# STM32F103C8T6.net
KiCad netlist of a schematic drawn in Altium Designer
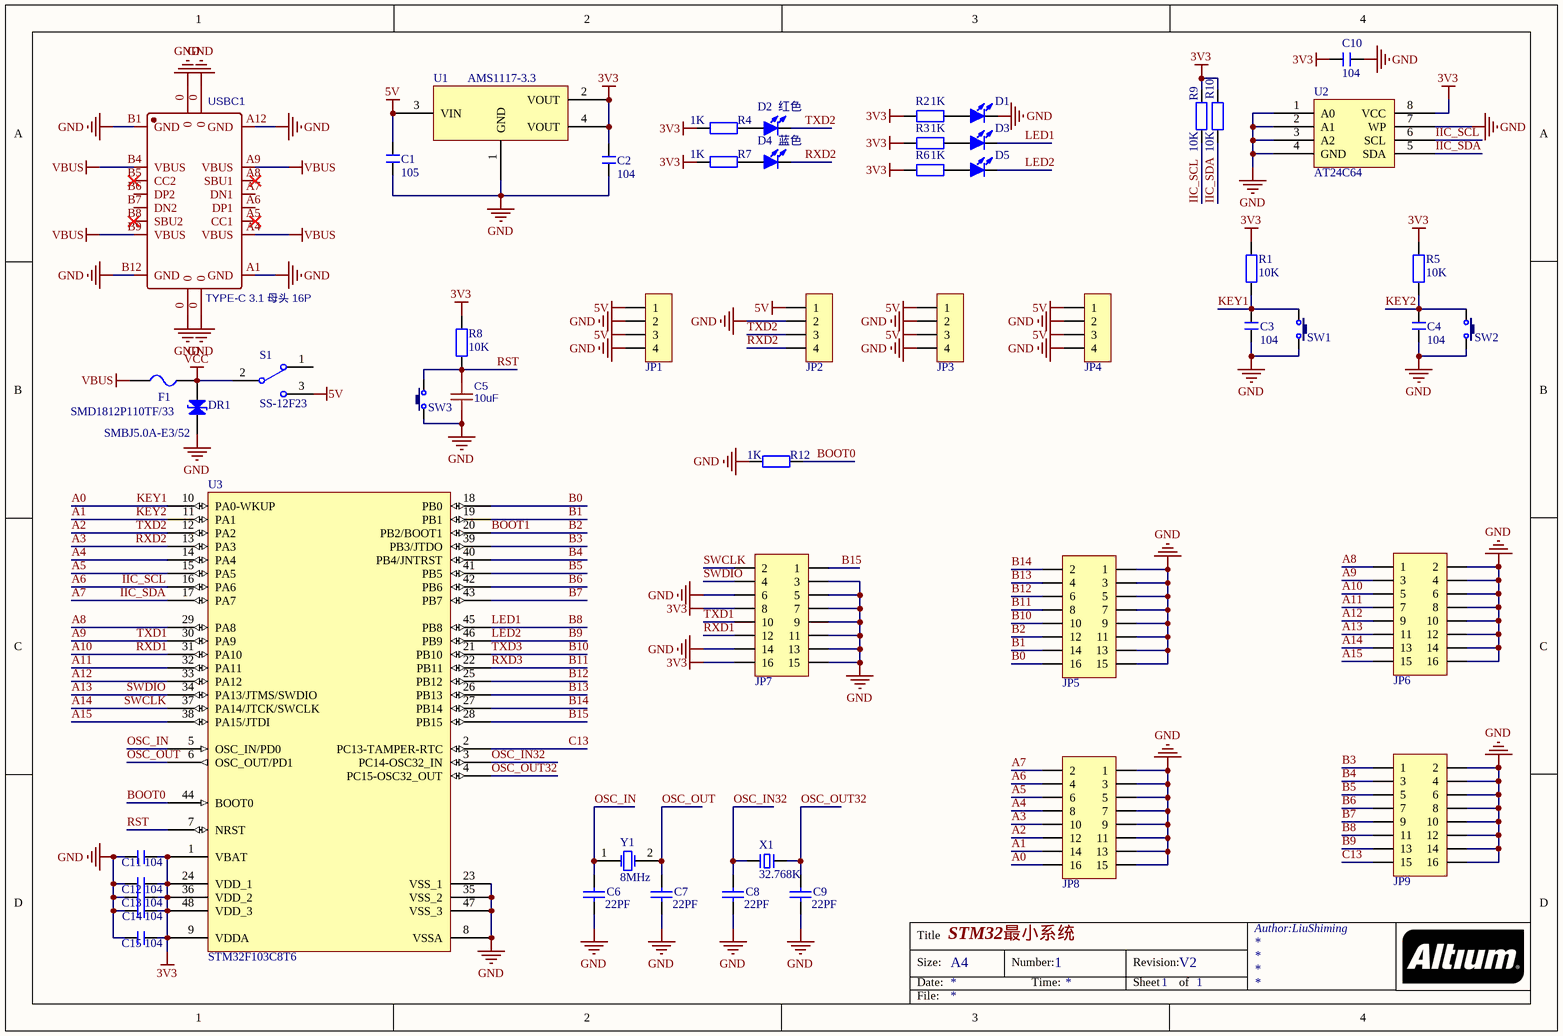
[diagram p0: STM32F103C8T6.SchDoc]

(export (version "E")
  (design (tool "Eeschema 10.0.6"))
  (components
    (comp (ref "C1")
      (value "105")
      (footprint "C 0603")
      (description "无极性贴片电容")
      (fields (field (name "版权归属") "源创客"))
      (libsource (lib "电阻-电容-电感") (part "C"))
    )
    (comp (ref "C2")
      (value "104")
      (footprint "C 0603")
      (description "无极性贴片电容")
      (fields (field (name "版权归属") "源创客"))
      (libsource (lib "电阻-电容-电感") (part "C"))
    )
    (comp (ref "C3")
      (value "104")
      (footprint "C 0603")
      (description "无极性贴片电容")
      (fields (field (name "版权归属") "源创客"))
      (libsource (lib "电阻-电容-电感") (part "C"))
    )
    (comp (ref "C4")
      (value "104")
      (footprint "C 0603")
      (description "无极性贴片电容")
      (fields (field (name "版权归属") "源创客"))
      (libsource (lib "电阻-电容-电感") (part "C"))
    )
    (comp (ref "C5")
      (value "10uF")
      (footprint "C 0603")
      (fields
        (field (name "BOM_SUPPLIER PART") "C327012")
        (field (name "BOM_MANUFACTURER PART") "CC0603GRNPO9BN300")
        (field (name "CONTRIBUTOR") "LCSC")
      )
      (libsource (lib "altium-import") (part "root_1_100nF_"))
    )
    (comp (ref "C6")
      (value "22PF")
      (footprint "C 0603")
      (description "Capacitor")
      (fields (field (name "PUBLISHER") "Altium Limited"))
      (libsource (lib "Miscellaneous Devices") (part "Cap"))
    )
    (comp (ref "C7")
      (value "22PF")
      (footprint "C 0603")
      (description "Capacitor")
      (fields (field (name "PUBLISHER") "Altium Limited"))
      (libsource (lib "Miscellaneous Devices") (part "Cap"))
    )
    (comp (ref "C8")
      (value "22PF")
      (footprint "C 0603")
      (description "Capacitor")
      (fields (field (name "PUBLISHER") "Altium Limited"))
      (libsource (lib "Miscellaneous Devices") (part "Cap"))
    )
    (comp (ref "C9")
      (value "22PF")
      (footprint "C 0603")
      (description "Capacitor")
      (fields (field (name "PUBLISHER") "Altium Limited"))
      (libsource (lib "Miscellaneous Devices") (part "Cap"))
    )
    (comp (ref "C10")
      (value "104")
      (footprint "C 0603")
      (description "无极性贴片电容")
      (fields (field (name "版权归属") "源创客"))
      (libsource (lib "电阻-电容-电感") (part "C"))
    )
    (comp (ref "C11")
      (value "104")
      (footprint "C 0603")
      (description "无极性贴片电容")
      (fields (field (name "版权归属") "源创客"))
      (libsource (lib "电阻-电容-电感") (part "C"))
    )
    (comp (ref "C12")
      (value "104")
      (footprint "C 0603")
      (description "无极性贴片电容")
      (fields (field (name "版权归属") "源创客"))
      (libsource (lib "电阻-电容-电感") (part "C"))
    )
    (comp (ref "C13")
      (value "104")
      (footprint "C 0603")
      (description "无极性贴片电容")
      (fields (field (name "版权归属") "源创客"))
      (libsource (lib "电阻-电容-电感") (part "C"))
    )
    (comp (ref "C14")
      (value "104")
      (footprint "C 0603")
      (description "无极性贴片电容")
      (fields (field (name "版权归属") "源创客"))
      (libsource (lib "电阻-电容-电感") (part "C"))
    )
    (comp (ref "C15")
      (value "104")
      (footprint "C 0603")
      (description "无极性贴片电容")
      (fields (field (name "版权归属") "源创客"))
      (libsource (lib "电阻-电容-电感") (part "C"))
    )
    (comp (ref "D1")
      (value "红色")
      (footprint "LED 0603R")
      (description "大功率LED")
      (fields (field (name "版权归属") "源创客"))
      (libsource (lib "LED") (part "LED-SMD_1W"))
    )
    (comp (ref "D2")
      (value "红色")
      (footprint "LED 0603R")
      (description "插件LED")
      (fields (field (name "版权归属") "源创客"))
      (libsource (lib "LED") (part "LED-3MM"))
    )
    (comp (ref "D3")
      (value "蓝色")
      (footprint "LED 0603B")
      (description "大功率LED")
      (fields (field (name "版权归属") "源创客"))
      (libsource (lib "LED") (part "LED-SMD_1W"))
    )
    (comp (ref "D4")
      (value "蓝色")
      (footprint "LED 0603B")
      (description "插件LED")
      (fields (field (name "版权归属") "源创客"))
      (libsource (lib "LED") (part "LED-3MM"))
    )
    (comp (ref "D5")
      (value "黄色")
      (footprint "LED 0603Y")
      (description "大功率LED")
      (fields (field (name "版权归属") "源创客"))
      (libsource (lib "LED") (part "LED-SMD_1W"))
    )
    (comp (ref "DR1")
      (value "SMBJ5.0A-E3/52")
      (footprint "SMB")
      (description "瞬态电压抑制二极管")
      (fields (field (name "版权归属") "源创客"))
      (libsource (lib "二极管-整流桥") (part "DR"))
    )
    (comp (ref "F1")
      (value "SMD1812P110TF/33")
      (footprint "FU 0805")
      (description "贴片保险丝")
      (fields (field (name "版权归属") "源创客"))
      (libsource (lib "保险丝-晶振") (part "FU"))
    )
    (comp (ref "JP1")
      (value "HDR-1X4")
      (footprint "HDR-1X4")
      (description "4P接插件")
      (fields (field (name "版权归属") "源创客"))
      (libsource (lib "接插件") (part "Header 4"))
    )
    (comp (ref "JP2")
      (value "HDR-1X4")
      (footprint "HDR-1X4")
      (description "4P接插件")
      (fields (field (name "版权归属") "源创客"))
      (libsource (lib "接插件") (part "Header 4"))
    )
    (comp (ref "JP3")
      (value "HDR-1X4")
      (footprint "HDR-1X4")
      (description "4P接插件")
      (fields (field (name "版权归属") "源创客"))
      (libsource (lib "接插件") (part "Header 4"))
    )
    (comp (ref "JP4")
      (value "HDR-1X4")
      (footprint "HDR-1X4")
      (description "4P接插件")
      (fields (field (name "版权归属") "源创客"))
      (libsource (lib "接插件") (part "Header 4"))
    )
    (comp (ref "JP5")
      (value "Header 8X2")
      (footprint "HD8X2")
      (description "8*2P接插件")
      (fields (field (name "版权归属") "源创客"))
      (libsource (lib "接插件") (part "Header 8X2"))
    )
    (comp (ref "JP6")
      (value "Header 8X2")
      (footprint "HD8X2")
      (description "8*2P接插件")
      (fields (field (name "版权归属") "源创客"))
      (libsource (lib "") (part "Header 8X2_1"))
    )
    (comp (ref "JP7")
      (value "Header 8X2")
      (footprint "HD8X2")
      (description "8*2P接插件")
      (fields (field (name "版权归属") "源创客"))
      (libsource (lib "接插件") (part "Header 8X2"))
    )
    (comp (ref "JP8")
      (value "Header 8X2")
      (footprint "HD8X2")
      (description "8*2P接插件")
      (fields (field (name "版权归属") "源创客"))
      (libsource (lib "接插件") (part "Header 8X2"))
    )
    (comp (ref "JP9")
      (value "Header 8X2")
      (footprint "HD8X2")
      (description "8*2P接插件")
      (fields (field (name "版权归属") "源创客"))
      (libsource (lib "") (part "Header 8X2_1"))
    )
    (comp (ref "R1")
      (value "10K")
      (footprint "R 0603")
      (description "贴片电阻")
      (fields (field (name "版权归属") "源创客"))
      (libsource (lib "UWB") (part "R"))
    )
    (comp (ref "R2")
      (value "1K")
      (footprint "R 0603")
      (description "大功率电阻")
      (fields (field (name "版权归属") "源创客"))
      (libsource (lib "电阻-电容-电感") (part "RX"))
    )
    (comp (ref "R3")
      (value "1K")
      (footprint "R 0603")
      (description "大功率电阻")
      (fields (field (name "版权归属") "源创客"))
      (libsource (lib "电阻-电容-电感") (part "RX"))
    )
    (comp (ref "R4")
      (value "1K")
      (footprint "R 0603")
      (description "贴片电阻")
      (fields (field (name "版权归属") "源创客"))
      (libsource (lib "电阻-电容-电感") (part "R"))
    )
    (comp (ref "R5")
      (value "10K")
      (footprint "R 0603")
      (description "贴片电阻")
      (fields (field (name "版权归属") "源创客"))
      (libsource (lib "UWB") (part "R"))
    )
    (comp (ref "R6")
      (value "1K")
      (footprint "R 0603")
      (description "大功率电阻")
      (fields (field (name "版权归属") "源创客"))
      (libsource (lib "电阻-电容-电感") (part "RX"))
    )
    (comp (ref "R7")
      (value "1K")
      (footprint "R 0603")
      (description "贴片电阻")
      (fields (field (name "版权归属") "源创客"))
      (libsource (lib "电阻-电容-电感") (part "R"))
    )
    (comp (ref "R8")
      (value "10K")
      (footprint "R 0603")
      (description "贴片电阻")
      (fields (field (name "版权归属") "源创客"))
      (libsource (lib "电阻-电容-电感") (part "R"))
    )
    (comp (ref "R9")
      (value "10K")
      (footprint "R 0603")
      (description "大功率电阻")
      (fields (field (name "版权归属") "源创客"))
      (libsource (lib "电阻-电容-电感") (part "RX"))
    )
    (comp (ref "R10")
      (value "10K")
      (footprint "R 0603")
      (description "大功率电阻")
      (fields (field (name "版权归属") "源创客"))
      (libsource (lib "电阻-电容-电感") (part "RX"))
    )
    (comp (ref "R12")
      (value "1K")
      (footprint "R 0603")
      (description "大功率电阻")
      (fields (field (name "版权归属") "源创客"))
      (libsource (lib "电阻-电容-电感") (part "RX"))
    )
    (comp (ref "S1")
      (value "SS-12F23")
      (footprint "MSK-12C01-07")
      (description "1路波动开关")
      (fields (field (name "版权归属") "源创客"))
      (libsource (lib "UWB") (part "SSW-1P"))
    )
    (comp (ref "SW1")
      (value "3x6x5")
      (footprint "TSW SMD-3*6*4.3")
      (description "3x6轻触开关")
      (fields (field (name "版权归属") "源创客"))
      (libsource (lib "UWB") (part "TSW 3x6"))
    )
    (comp (ref "SW2")
      (value "3x6x5")
      (footprint "TSW SMD-3*6*4.3")
      (description "3x6轻触开关")
      (fields (field (name "版权归属") "源创客"))
      (libsource (lib "UWB") (part "TSW 3x6"))
    )
    (comp (ref "SW3")
      (value "3x6x5")
      (footprint "TSW SMD-3*6*4.3")
      (description "3x6轻触开关")
      (fields (field (name "版权归属") "源创客"))
      (libsource (lib "") (part "TSW 3x6_1"))
    )
    (comp (ref "U1")
      (value "AMS1117-3.3")
      (footprint "SOT223_N")
      (libsource (lib "步进电机控制模块") (part "AMS1117_3.3V"))
    )
    (comp (ref "U2") (value "AT24C64") (footprint "SOP8_N") (libsource (lib "UWB") (part "AT24C64")))
    (comp (ref "U3")
      (value "STM32F103C8T6")
      (footprint "LQFP48_M")
      (description "STM32 ARM-based 32-bit MCU with 64 Kbytes Flash, 48-pin LQFP, Industrial Temperature")
      (fields (field (name "PUBLISHER") "Altium Limited"))
      (libsource (lib "ST Microcontroller 32-Bit STM32") (part "STM32F103C8T6"))
    )
    (comp (ref "USBC1")
      (value "TYPE-C 3.1 母头 16P")
      (footprint "USB-TYPE-C_16PIN-MALE-TYPE-C-31-M-12")
      (libsource (lib "type-c-sch") (part "TYPE-C 3.1 母头 16P"))
    )
    (comp (ref "X1")
      (value "32.768K")
      (footprint "XTAL-3X8H")
      (description "2脚晶振")
      (fields (field (name "版权归属") "源创客"))
      (libsource (lib "保险丝-晶振") (part "XTAL-2"))
    )
    (comp (ref "Y1")
      (value "8MHz")
      (footprint "XTAL-49S DIP")
      (description "Crystal Oscillator")
      (fields (field (name "PUBLISHER") "Altium Limited"))
      (libsource (lib "Miscellaneous Devices") (part "XTAL"))
    )
  )
  (nets
    (net (code "1") (name "/A0") (class "Default")
      (node (ref "C3") (pin "2") (pinfunction "2_2") (pintype "passive"))
      (node (ref "JP8") (pin "16") (pinfunction "16_16") (pintype "passive"))
      (node (ref "R1") (pin "1") (pinfunction "1_1") (pintype "passive"))
      (node (ref "SW1") (pin "1") (pinfunction "1_1") (pintype "passive"))
      (node (ref "U3") (pin "10") (pinfunction "PA0-WKUP_10") (pintype "bidirectional"))
    )
    (net (code "2") (name "/A1") (class "Default")
      (node (ref "C4") (pin "2") (pinfunction "2_2") (pintype "passive"))
      (node (ref "JP8") (pin "14") (pinfunction "14_14") (pintype "passive"))
      (node (ref "R5") (pin "1") (pinfunction "1_1") (pintype "passive"))
      (node (ref "SW2") (pin "1") (pinfunction "1_1") (pintype "passive"))
      (node (ref "U3") (pin "11") (pinfunction "PA1_11") (pintype "bidirectional"))
    )
    (net (code "3") (name "/A2") (class "Default")
      (node (ref "D2") (pin "2") (pinfunction "K_2") (pintype "passive"))
      (node (ref "JP2") (pin "3") (pinfunction "3_3") (pintype "passive"))
      (node (ref "JP8") (pin "12") (pinfunction "12_12") (pintype "passive"))
      (node (ref "U3") (pin "12") (pinfunction "PA2_12") (pintype "bidirectional"))
    )
    (net (code "4") (name "/A3") (class "Default")
      (node (ref "D4") (pin "2") (pinfunction "K_2") (pintype "passive"))
      (node (ref "JP2") (pin "4") (pinfunction "4_4") (pintype "passive"))
      (node (ref "JP8") (pin "10") (pinfunction "10_10") (pintype "passive"))
      (node (ref "U3") (pin "13") (pinfunction "PA3_13") (pintype "bidirectional"))
    )
    (net (code "5") (name "/A4") (class "Default")
      (node (ref "JP8") (pin "8") (pinfunction "8_8") (pintype "passive"))
      (node (ref "U3") (pin "14") (pinfunction "PA4_14") (pintype "bidirectional"))
    )
    (net (code "6") (name "/A5") (class "Default")
      (node (ref "JP8") (pin "6") (pinfunction "6_6") (pintype "passive"))
      (node (ref "U3") (pin "15") (pinfunction "PA5_15") (pintype "bidirectional"))
    )
    (net (code "7") (name "/A6") (class "Default")
      (node (ref "JP8") (pin "4") (pinfunction "4_4") (pintype "passive"))
      (node (ref "R9") (pin "2") (pinfunction "2_2") (pintype "passive"))
      (node (ref "U2") (pin "6") (pinfunction "SCL_6") (pintype "passive"))
      (node (ref "U3") (pin "16") (pinfunction "PA6_16") (pintype "bidirectional"))
    )
    (net (code "8") (name "/A7") (class "Default")
      (node (ref "JP8") (pin "2") (pinfunction "2_2") (pintype "passive"))
      (node (ref "R10") (pin "2") (pinfunction "2_2") (pintype "passive"))
      (node (ref "U2") (pin "5") (pinfunction "SDA_5") (pintype "passive"))
      (node (ref "U3") (pin "17") (pinfunction "PA7_17") (pintype "bidirectional"))
    )
    (net (code "9") (name "/A8") (class "Default")
      (node (ref "JP6") (pin "1") (pinfunction "1_1") (pintype "passive"))
      (node (ref "U3") (pin "29") (pinfunction "PA8_29") (pintype "bidirectional"))
    )
    (net (code "10") (name "/A9") (class "Default")
      (node (ref "JP6") (pin "3") (pinfunction "3_3") (pintype "passive"))
      (node (ref "JP7") (pin "10") (pinfunction "10_10") (pintype "passive"))
      (node (ref "U3") (pin "30") (pinfunction "PA9_30") (pintype "bidirectional"))
    )
    (net (code "11") (name "/A10") (class "Default")
      (node (ref "JP6") (pin "5") (pinfunction "5_5") (pintype "passive"))
      (node (ref "JP7") (pin "12") (pinfunction "12_12") (pintype "passive"))
      (node (ref "U3") (pin "31") (pinfunction "PA10_31") (pintype "bidirectional"))
    )
    (net (code "12") (name "/A11") (class "Default")
      (node (ref "JP6") (pin "7") (pinfunction "7_7") (pintype "passive"))
      (node (ref "U3") (pin "32") (pinfunction "PA11_32") (pintype "bidirectional"))
    )
    (net (code "13") (name "/A12") (class "Default")
      (node (ref "JP6") (pin "9") (pinfunction "9_9") (pintype "passive"))
      (node (ref "U3") (pin "33") (pinfunction "PA12_33") (pintype "bidirectional"))
    )
    (net (code "14") (name "/A13") (class "Default")
      (node (ref "JP6") (pin "11") (pinfunction "11_11") (pintype "passive"))
      (node (ref "JP7") (pin "4") (pinfunction "4_4") (pintype "passive"))
      (node (ref "U3") (pin "34") (pinfunction "PA13/JTMS/SWDIO_34") (pintype "bidirectional"))
    )
    (net (code "15") (name "/A14") (class "Default")
      (node (ref "JP6") (pin "13") (pinfunction "13_13") (pintype "passive"))
      (node (ref "JP7") (pin "2") (pinfunction "2_2") (pintype "passive"))
      (node (ref "U3") (pin "37") (pinfunction "PA14/JTCK/SWCLK_37") (pintype "bidirectional"))
    )
    (net (code "16") (name "/A15") (class "Default")
      (node (ref "JP6") (pin "15") (pinfunction "15_15") (pintype "passive"))
      (node (ref "U3") (pin "38") (pinfunction "PA15/JTDI_38") (pintype "bidirectional"))
    )
    (net (code "17") (name "/B0") (class "Default")
      (node (ref "JP5") (pin "16") (pinfunction "16_16") (pintype "passive"))
      (node (ref "U3") (pin "18") (pinfunction "PB0_18") (pintype "bidirectional"))
    )
    (net (code "18") (name "/B1") (class "Default")
      (node (ref "JP5") (pin "14") (pinfunction "14_14") (pintype "passive"))
      (node (ref "U3") (pin "19") (pinfunction "PB1_19") (pintype "bidirectional"))
    )
    (net (code "19") (name "/B2") (class "Default")
      (node (ref "JP5") (pin "12") (pinfunction "12_12") (pintype "passive"))
      (node (ref "U3") (pin "20") (pinfunction "PB2/BOOT1_20") (pintype "bidirectional"))
    )
    (net (code "20") (name "/B3") (class "Default")
      (node (ref "JP9") (pin "1") (pinfunction "1_1") (pintype "passive"))
      (node (ref "U3") (pin "39") (pinfunction "PB3/JTDO_39") (pintype "bidirectional"))
    )
    (net (code "21") (name "/B4") (class "Default")
      (node (ref "JP9") (pin "3") (pinfunction "3_3") (pintype "passive"))
      (node (ref "U3") (pin "40") (pinfunction "PB4/JNTRST_40") (pintype "bidirectional"))
    )
    (net (code "22") (name "/B5") (class "Default")
      (node (ref "JP9") (pin "5") (pinfunction "5_5") (pintype "passive"))
      (node (ref "U3") (pin "41") (pinfunction "PB5_41") (pintype "bidirectional"))
    )
    (net (code "23") (name "/B6") (class "Default")
      (node (ref "JP9") (pin "7") (pinfunction "7_7") (pintype "passive"))
      (node (ref "U3") (pin "42") (pinfunction "PB6_42") (pintype "bidirectional"))
    )
    (net (code "24") (name "/B7") (class "Default")
      (node (ref "JP9") (pin "9") (pinfunction "9_9") (pintype "passive"))
      (node (ref "U3") (pin "43") (pinfunction "PB7_43") (pintype "bidirectional"))
    )
    (net (code "25") (name "/B8") (class "Default")
      (node (ref "D3") (pin "2") (pinfunction "K_2") (pintype "passive"))
      (node (ref "JP9") (pin "11") (pinfunction "11_11") (pintype "passive"))
      (node (ref "U3") (pin "45") (pinfunction "PB8_45") (pintype "bidirectional"))
    )
    (net (code "26") (name "/B9") (class "Default")
      (node (ref "D5") (pin "2") (pinfunction "K_2") (pintype "passive"))
      (node (ref "JP9") (pin "13") (pinfunction "13_13") (pintype "passive"))
      (node (ref "U3") (pin "46") (pinfunction "PB9_46") (pintype "bidirectional"))
    )
    (net (code "27") (name "/B10") (class "Default")
      (node (ref "JP5") (pin "10") (pinfunction "10_10") (pintype "passive"))
      (node (ref "U3") (pin "21") (pinfunction "PB10_21") (pintype "bidirectional"))
    )
    (net (code "28") (name "/B11") (class "Default")
      (node (ref "JP5") (pin "8") (pinfunction "8_8") (pintype "passive"))
      (node (ref "U3") (pin "22") (pinfunction "PB11_22") (pintype "bidirectional"))
    )
    (net (code "29") (name "/B12") (class "Default")
      (node (ref "JP5") (pin "6") (pinfunction "6_6") (pintype "passive"))
      (node (ref "U3") (pin "25") (pinfunction "PB12_25") (pintype "bidirectional"))
    )
    (net (code "30") (name "/B13") (class "Default")
      (node (ref "JP5") (pin "4") (pinfunction "4_4") (pintype "passive"))
      (node (ref "U3") (pin "26") (pinfunction "PB13_26") (pintype "bidirectional"))
    )
    (net (code "31") (name "/B14") (class "Default")
      (node (ref "JP5") (pin "2") (pinfunction "2_2") (pintype "passive"))
      (node (ref "U3") (pin "27") (pinfunction "PB14_27") (pintype "bidirectional"))
    )
    (net (code "32") (name "/B15") (class "Default")
      (node (ref "JP7") (pin "1") (pinfunction "1_1") (pintype "passive"))
      (node (ref "U3") (pin "28") (pinfunction "PB15_28") (pintype "bidirectional"))
    )
    (net (code "33") (name "/BOOT0") (class "Default")
      (node (ref "R12") (pin "2") (pinfunction "2_2") (pintype "passive"))
      (node (ref "U3") (pin "44") (pinfunction "BOOT0_44") (pintype "input"))
    )
    (net (code "34") (name "/C13") (class "Default")
      (node (ref "JP9") (pin "15") (pinfunction "15_15") (pintype "passive"))
      (node (ref "U3") (pin "2") (pinfunction "PC13-TAMPER-RTC_2") (pintype "bidirectional"))
    )
    (net (code "35") (name "/OSC_IN") (class "Default")
      (node (ref "C6") (pin "1") (pinfunction "1_1") (pintype "passive"))
      (node (ref "U3") (pin "5") (pinfunction "OSC_IN/PD0_5") (pintype "input"))
      (node (ref "Y1") (pin "1") (pinfunction "OSC1_1") (pintype "passive"))
    )
    (net (code "36") (name "/OSC_IN32") (class "Default")
      (node (ref "C8") (pin "1") (pinfunction "1_1") (pintype "passive"))
      (node (ref "U3") (pin "3") (pinfunction "PC14-OSC32_IN_3") (pintype "bidirectional"))
      (node (ref "X1") (pin "1") (pinfunction "1_1") (pintype "passive"))
    )
    (net (code "37") (name "/OSC_OUT") (class "Default")
      (node (ref "C7") (pin "1") (pinfunction "1_1") (pintype "passive"))
      (node (ref "U3") (pin "6") (pinfunction "OSC_OUT/PD1_6") (pintype "output"))
      (node (ref "Y1") (pin "2") (pinfunction "OSC2_2") (pintype "passive"))
    )
    (net (code "38") (name "/OSC_OUT32") (class "Default")
      (node (ref "C9") (pin "1") (pinfunction "1_1") (pintype "passive"))
      (node (ref "U3") (pin "4") (pinfunction "PC15-OSC32_OUT_4") (pintype "bidirectional"))
      (node (ref "X1") (pin "2") (pinfunction "2_2") (pintype "passive"))
    )
    (net (code "39") (name "/RST") (class "Default")
      (node (ref "C5") (pin "1") (pinfunction "1_1") (pintype "passive"))
      (node (ref "R8") (pin "2") (pinfunction "2_2") (pintype "passive"))
      (node (ref "SW3") (pin "2") (pinfunction "2_2") (pintype "passive"))
      (node (ref "U3") (pin "7") (pinfunction "NRST_7") (pintype "bidirectional"))
    )
    (net (code "40") (name "3V3") (class "Default")
      (node (ref "C10") (pin "2") (pinfunction "2_2") (pintype "passive"))
      (node (ref "C11") (pin "1") (pinfunction "1_1") (pintype "passive"))
      (node (ref "C12") (pin "1") (pinfunction "1_1") (pintype "passive"))
      (node (ref "C13") (pin "1") (pinfunction "1_1") (pintype "passive"))
      (node (ref "C14") (pin "1") (pinfunction "1_1") (pintype "passive"))
      (node (ref "C15") (pin "1") (pinfunction "1_1") (pintype "passive"))
      (node (ref "C2") (pin "2") (pinfunction "2_2") (pintype "passive"))
      (node (ref "JP7") (pin "16") (pinfunction "16_16") (pintype "passive"))
      (node (ref "JP7") (pin "8") (pinfunction "8_8") (pintype "passive"))
      (node (ref "R1") (pin "2") (pinfunction "2_2") (pintype "passive"))
      (node (ref "R10") (pin "1") (pinfunction "1_1") (pintype "passive"))
      (node (ref "R2") (pin "1") (pinfunction "1_1") (pintype "passive"))
      (node (ref "R3") (pin "1") (pinfunction "1_1") (pintype "passive"))
      (node (ref "R4") (pin "1") (pinfunction "1_1") (pintype "passive"))
      (node (ref "R5") (pin "2") (pinfunction "2_2") (pintype "passive"))
      (node (ref "R6") (pin "1") (pinfunction "1_1") (pintype "passive"))
      (node (ref "R7") (pin "1") (pinfunction "1_1") (pintype "passive"))
      (node (ref "R8") (pin "1") (pinfunction "1_1") (pintype "passive"))
      (node (ref "R9") (pin "1") (pinfunction "1_1") (pintype "passive"))
      (node (ref "U1") (pin "2") (pinfunction "VOUT_2") (pintype "passive"))
      (node (ref "U1") (pin "4") (pinfunction "VOUT_4") (pintype "passive"))
      (node (ref "U2") (pin "8") (pinfunction "VCC_8") (pintype "passive"))
      (node (ref "U3") (pin "1") (pinfunction "VBAT_1") (pintype "power_in"))
      (node (ref "U3") (pin "24") (pinfunction "VDD_1_24") (pintype "power_in"))
      (node (ref "U3") (pin "36") (pinfunction "VDD_2_36") (pintype "power_in"))
      (node (ref "U3") (pin "48") (pinfunction "VDD_3_48") (pintype "power_in"))
      (node (ref "U3") (pin "9") (pinfunction "VDDA_9") (pintype "power_in"))
    )
    (net (code "41") (name "5V") (class "Default")
      (node (ref "C1") (pin "2") (pinfunction "2_2") (pintype "passive"))
      (node (ref "JP1") (pin "1") (pinfunction "1_1") (pintype "passive"))
      (node (ref "JP1") (pin "3") (pinfunction "3_3") (pintype "passive"))
      (node (ref "JP2") (pin "1") (pinfunction "1_1") (pintype "passive"))
      (node (ref "JP3") (pin "1") (pinfunction "1_1") (pintype "passive"))
      (node (ref "JP3") (pin "3") (pinfunction "3_3") (pintype "passive"))
      (node (ref "JP4") (pin "1") (pinfunction "1_1") (pintype "passive"))
      (node (ref "JP4") (pin "3") (pinfunction "3_3") (pintype "passive"))
      (node (ref "S1") (pin "3") (pinfunction "3_3") (pintype "passive"))
      (node (ref "U1") (pin "3") (pinfunction "VIN_3") (pintype "passive"))
    )
    (net (code "42") (name "GND") (class "Default")
      (node (ref "C1") (pin "1") (pinfunction "1_1") (pintype "passive"))
      (node (ref "C10") (pin "1") (pinfunction "1_1") (pintype "passive"))
      (node (ref "C11") (pin "2") (pinfunction "2_2") (pintype "passive"))
      (node (ref "C12") (pin "2") (pinfunction "2_2") (pintype "passive"))
      (node (ref "C13") (pin "2") (pinfunction "2_2") (pintype "passive"))
      (node (ref "C14") (pin "2") (pinfunction "2_2") (pintype "passive"))
      (node (ref "C15") (pin "2") (pinfunction "2_2") (pintype "passive"))
      (node (ref "C2") (pin "1") (pinfunction "1_1") (pintype "passive"))
      (node (ref "C3") (pin "1") (pinfunction "1_1") (pintype "passive"))
      (node (ref "C4") (pin "1") (pinfunction "1_1") (pintype "passive"))
      (node (ref "C5") (pin "2") (pinfunction "2_2") (pintype "passive"))
      (node (ref "C6") (pin "2") (pinfunction "2_2") (pintype "passive"))
      (node (ref "C7") (pin "2") (pinfunction "2_2") (pintype "passive"))
      (node (ref "C8") (pin "2") (pinfunction "2_2") (pintype "passive"))
      (node (ref "C9") (pin "2") (pinfunction "2_2") (pintype "passive"))
      (node (ref "D1") (pin "2") (pinfunction "K_2") (pintype "passive"))
      (node (ref "DR1") (pin "1") (pinfunction "A_1") (pintype "passive"))
      (node (ref "JP1") (pin "2") (pinfunction "2_2") (pintype "passive"))
      (node (ref "JP1") (pin "4") (pinfunction "4_4") (pintype "passive"))
      (node (ref "JP2") (pin "2") (pinfunction "2_2") (pintype "passive"))
      (node (ref "JP3") (pin "2") (pinfunction "2_2") (pintype "passive"))
      (node (ref "JP3") (pin "4") (pinfunction "4_4") (pintype "passive"))
      (node (ref "JP4") (pin "2") (pinfunction "2_2") (pintype "passive"))
      (node (ref "JP4") (pin "4") (pinfunction "4_4") (pintype "passive"))
      (node (ref "JP5") (pin "1") (pinfunction "1_1") (pintype "passive"))
      (node (ref "JP5") (pin "11") (pinfunction "11_11") (pintype "passive"))
      (node (ref "JP5") (pin "13") (pinfunction "13_13") (pintype "passive"))
      (node (ref "JP5") (pin "15") (pinfunction "15_15") (pintype "passive"))
      (node (ref "JP5") (pin "3") (pinfunction "3_3") (pintype "passive"))
      (node (ref "JP5") (pin "5") (pinfunction "5_5") (pintype "passive"))
      (node (ref "JP5") (pin "7") (pinfunction "7_7") (pintype "passive"))
      (node (ref "JP5") (pin "9") (pinfunction "9_9") (pintype "passive"))
      (node (ref "JP6") (pin "10") (pinfunction "10_10") (pintype "passive"))
      (node (ref "JP6") (pin "12") (pinfunction "12_12") (pintype "passive"))
      (node (ref "JP6") (pin "14") (pinfunction "14_14") (pintype "passive"))
      (node (ref "JP6") (pin "16") (pinfunction "16_16") (pintype "passive"))
      (node (ref "JP6") (pin "2") (pinfunction "2_2") (pintype "passive"))
      (node (ref "JP6") (pin "4") (pinfunction "4_4") (pintype "passive"))
      (node (ref "JP6") (pin "6") (pinfunction "6_6") (pintype "passive"))
      (node (ref "JP6") (pin "8") (pinfunction "8_8") (pintype "passive"))
      (node (ref "JP7") (pin "11") (pinfunction "11_11") (pintype "passive"))
      (node (ref "JP7") (pin "13") (pinfunction "13_13") (pintype "passive"))
      (node (ref "JP7") (pin "14") (pinfunction "14_14") (pintype "passive"))
      (node (ref "JP7") (pin "15") (pinfunction "15_15") (pintype "passive"))
      (node (ref "JP7") (pin "3") (pinfunction "3_3") (pintype "passive"))
      (node (ref "JP7") (pin "5") (pinfunction "5_5") (pintype "passive"))
      (node (ref "JP7") (pin "6") (pinfunction "6_6") (pintype "passive"))
      (node (ref "JP7") (pin "7") (pinfunction "7_7") (pintype "passive"))
      (node (ref "JP7") (pin "9") (pinfunction "9_9") (pintype "passive"))
      (node (ref "JP8") (pin "1") (pinfunction "1_1") (pintype "passive"))
      (node (ref "JP8") (pin "11") (pinfunction "11_11") (pintype "passive"))
      (node (ref "JP8") (pin "13") (pinfunction "13_13") (pintype "passive"))
      (node (ref "JP8") (pin "15") (pinfunction "15_15") (pintype "passive"))
      (node (ref "JP8") (pin "3") (pinfunction "3_3") (pintype "passive"))
      (node (ref "JP8") (pin "5") (pinfunction "5_5") (pintype "passive"))
      (node (ref "JP8") (pin "7") (pinfunction "7_7") (pintype "passive"))
      (node (ref "JP8") (pin "9") (pinfunction "9_9") (pintype "passive"))
      (node (ref "JP9") (pin "10") (pinfunction "10_10") (pintype "passive"))
      (node (ref "JP9") (pin "12") (pinfunction "12_12") (pintype "passive"))
      (node (ref "JP9") (pin "14") (pinfunction "14_14") (pintype "passive"))
      (node (ref "JP9") (pin "16") (pinfunction "16_16") (pintype "passive"))
      (node (ref "JP9") (pin "2") (pinfunction "2_2") (pintype "passive"))
      (node (ref "JP9") (pin "4") (pinfunction "4_4") (pintype "passive"))
      (node (ref "JP9") (pin "6") (pinfunction "6_6") (pintype "passive"))
      (node (ref "JP9") (pin "8") (pinfunction "8_8") (pintype "passive"))
      (node (ref "R12") (pin "1") (pinfunction "1_1") (pintype "passive"))
      (node (ref "SW1") (pin "2") (pinfunction "2_2") (pintype "passive"))
      (node (ref "SW2") (pin "2") (pinfunction "2_2") (pintype "passive"))
      (node (ref "SW3") (pin "1") (pinfunction "1_1") (pintype "passive"))
      (node (ref "U1") (pin "1") (pinfunction "GND_1") (pintype "passive"))
      (node (ref "U2") (pin "1") (pinfunction "A0_1") (pintype "passive"))
      (node (ref "U2") (pin "2") (pinfunction "A1_2") (pintype "passive"))
      (node (ref "U2") (pin "3") (pinfunction "A2_3") (pintype "passive"))
      (node (ref "U2") (pin "4") (pinfunction "GND_4") (pintype "passive"))
      (node (ref "U2") (pin "7") (pinfunction "WP_7") (pintype "passive"))
      (node (ref "U3") (pin "23") (pinfunction "VSS_1_23") (pintype "power_in"))
      (node (ref "U3") (pin "35") (pinfunction "VSS_2_35") (pintype "power_in"))
      (node (ref "U3") (pin "47") (pinfunction "VSS_3_47") (pintype "power_in"))
      (node (ref "U3") (pin "8") (pinfunction "VSSA_8") (pintype "power_in"))
      (node (ref "USBC1") (pin "0") (pinfunction "0_0") (pintype "passive"))
      (node (ref "USBC1") (pin "A1") (pinfunction "GND_A1") (pintype "passive"))
      (node (ref "USBC1") (pin "A12") (pinfunction "GND_A12") (pintype "passive"))
      (node (ref "USBC1") (pin "B1") (pinfunction "GND_B1") (pintype "passive"))
      (node (ref "USBC1") (pin "B12") (pinfunction "GND_B12") (pintype "passive"))
    )
    (net (code "43") (name "Net-(D1-A)") (class "Default")
      (node (ref "D1") (pin "1") (pinfunction "A_1") (pintype "passive"))
      (node (ref "R2") (pin "2") (pinfunction "2_2") (pintype "passive"))
    )
    (net (code "44") (name "Net-(D2-A)") (class "Default")
      (node (ref "D2") (pin "1") (pinfunction "A_1") (pintype "passive"))
      (node (ref "R4") (pin "2") (pinfunction "2_2") (pintype "passive"))
    )
    (net (code "45") (name "Net-(D3-A)") (class "Default")
      (node (ref "D3") (pin "1") (pinfunction "A_1") (pintype "passive"))
      (node (ref "R3") (pin "2") (pinfunction "2_2") (pintype "passive"))
    )
    (net (code "46") (name "Net-(D4-A)") (class "Default")
      (node (ref "D4") (pin "1") (pinfunction "A_1") (pintype "passive"))
      (node (ref "R7") (pin "2") (pinfunction "2_2") (pintype "passive"))
    )
    (net (code "47") (name "Net-(D5-A)") (class "Default")
      (node (ref "D5") (pin "1") (pinfunction "A_1") (pintype "passive"))
      (node (ref "R6") (pin "2") (pinfunction "2_2") (pintype "passive"))
    )
    (net (code "48") (name "VBUS") (class "Default")
      (node (ref "F1") (pin "1") (pinfunction "1_1") (pintype "passive"))
      (node (ref "USBC1") (pin "A4") (pinfunction "VBUS_A4") (pintype "passive"))
      (node (ref "USBC1") (pin "A9") (pinfunction "VBUS_A9") (pintype "passive"))
      (node (ref "USBC1") (pin "B4") (pinfunction "VBUS_B4") (pintype "passive"))
      (node (ref "USBC1") (pin "B9") (pinfunction "VBUS_B9") (pintype "passive"))
    )
    (net (code "49") (name "VCC") (class "Default")
      (node (ref "DR1") (pin "2") (pinfunction "K_2") (pintype "passive"))
      (node (ref "F1") (pin "2") (pinfunction "2_2") (pintype "passive"))
      (node (ref "S1") (pin "2") (pinfunction "2_2") (pintype "passive"))
    )
    (net (code "50") (name "unconnected-(S1-Pad1)") (class "Default")
      (node (ref "S1") (pin "1") (pinfunction "1_1") (pintype "passive"))
    )
    (net (code "51") (name "unconnected-(USBC1-CC1-PadA5)") (class "Default")
      (node (ref "USBC1") (pin "A5") (pinfunction "CC1_A5") (pintype "passive+no_connect"))
    )
    (net (code "52") (name "unconnected-(USBC1-CC2-PadB5)") (class "Default")
      (node (ref "USBC1") (pin "B5") (pinfunction "CC2_B5") (pintype "passive+no_connect"))
    )
    (net (code "53") (name "unconnected-(USBC1-DN1-PadA7)") (class "Default")
      (node (ref "USBC1") (pin "A7") (pinfunction "DN1_A7") (pintype "passive"))
    )
    (net (code "54") (name "unconnected-(USBC1-DN2-PadB7)") (class "Default")
      (node (ref "USBC1") (pin "B7") (pinfunction "DN2_B7") (pintype "passive"))
    )
    (net (code "55") (name "unconnected-(USBC1-DP1-PadA6)") (class "Default")
      (node (ref "USBC1") (pin "A6") (pinfunction "DP1_A6") (pintype "passive"))
    )
    (net (code "56") (name "unconnected-(USBC1-DP2-PadB6)") (class "Default")
      (node (ref "USBC1") (pin "B6") (pinfunction "DP2_B6") (pintype "passive"))
    )
    (net (code "57") (name "unconnected-(USBC1-SBU1-PadA8)") (class "Default")
      (node (ref "USBC1") (pin "A8") (pinfunction "SBU1_A8") (pintype "passive+no_connect"))
    )
    (net (code "58") (name "unconnected-(USBC1-SBU2-PadB8)") (class "Default")
      (node (ref "USBC1") (pin "B8") (pinfunction "SBU2_B8") (pintype "passive+no_connect"))
    )
  )
)
